# Buttons.net
KiCad netlist of a schematic drawn in EAGLE
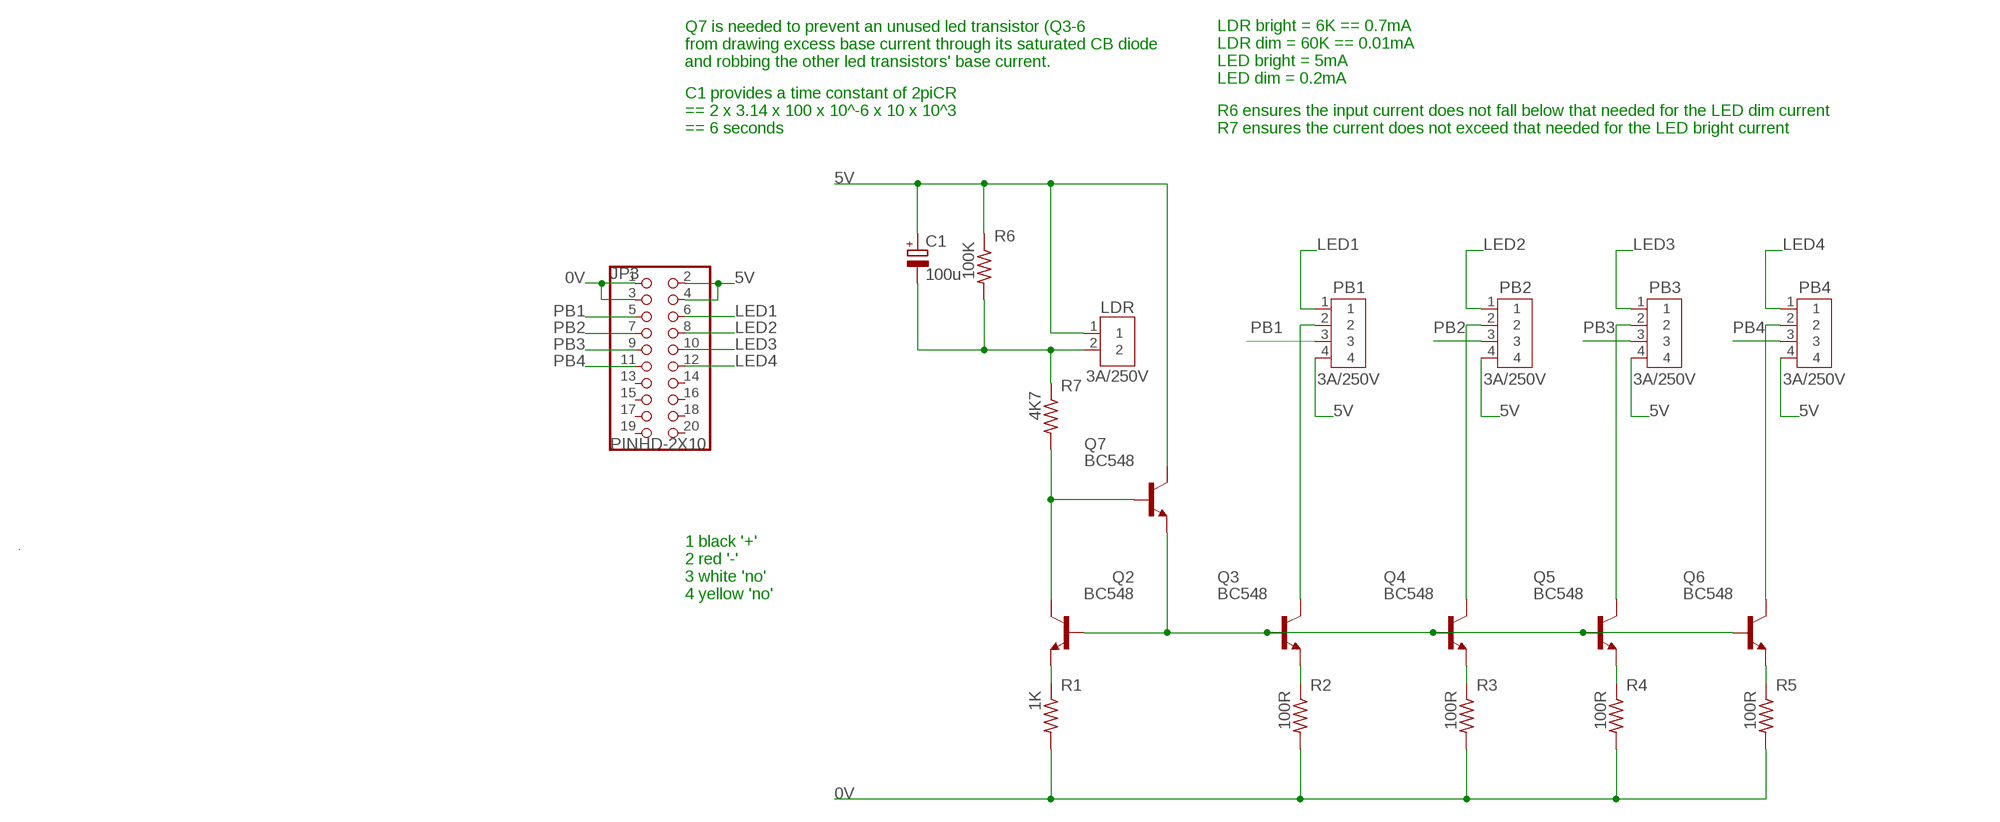
[diagram p0: schematic, sheet 1]

(export (version "E")
  (design (tool "Eeschema 10.0.6"))
  (components
    (comp (ref "C1")
      (value "100u")
      (footprint "eagle-import:E3,5-8")
      (libsource (lib "eagle-import") (part "CPOL-EUE3.5-8"))
    )
    (comp (ref "JP3")
      (value "PINHD-2X10")
      (footprint "eagle-import:2X10")
      (libsource (lib "eagle-import") (part "PINHD-2X10"))
    )
    (comp (ref "LDR")
      (value "3A/250V")
      (footprint "eagle-import:B2B-XH-A")
      (fields (field (name "MANUFACTURER") "JST (XH CONNECTOR)") (field (name "MPN") "B2B-XH-A"))
      (libsource (lib "eagle-import") (part "B2B-XH-A"))
    )
    (comp (ref "PB1")
      (value "3A/250V")
      (footprint "eagle-import:B4B-XH-A")
      (fields (field (name "MANUFACTURER") "JST (XH connector)") (field (name "MPN") "B4B-XH-A"))
      (libsource (lib "eagle-import") (part "B4B-XH-A"))
    )
    (comp (ref "PB2")
      (value "3A/250V")
      (footprint "eagle-import:B4B-XH-A")
      (fields (field (name "MANUFACTURER") "JST (XH connector)") (field (name "MPN") "B4B-XH-A"))
      (libsource (lib "eagle-import") (part "B4B-XH-A"))
    )
    (comp (ref "PB3")
      (value "3A/250V")
      (footprint "eagle-import:B4B-XH-A")
      (fields (field (name "MANUFACTURER") "JST (XH connector)") (field (name "MPN") "B4B-XH-A"))
      (libsource (lib "eagle-import") (part "B4B-XH-A"))
    )
    (comp (ref "PB4")
      (value "3A/250V")
      (footprint "eagle-import:B4B-XH-A")
      (fields (field (name "MANUFACTURER") "JST (XH connector)") (field (name "MPN") "B4B-XH-A"))
      (libsource (lib "eagle-import") (part "B4B-XH-A"))
    )
    (comp (ref "Q2")
      (value "BC548")
      (footprint "eagle-import:TO92-EBC")
      (libsource (lib "eagle-import") (part "BC548"))
    )
    (comp (ref "Q3")
      (value "BC548")
      (footprint "eagle-import:TO92-EBC")
      (libsource (lib "eagle-import") (part "BC548"))
    )
    (comp (ref "Q4")
      (value "BC548")
      (footprint "eagle-import:TO92-EBC")
      (libsource (lib "eagle-import") (part "BC548"))
    )
    (comp (ref "Q5")
      (value "BC548")
      (footprint "eagle-import:TO92-EBC")
      (libsource (lib "eagle-import") (part "BC548"))
    )
    (comp (ref "Q6")
      (value "BC548")
      (footprint "eagle-import:TO92-EBC")
      (libsource (lib "eagle-import") (part "BC548"))
    )
    (comp (ref "Q7")
      (value "BC548")
      (footprint "eagle-import:TO92-EBC")
      (libsource (lib "eagle-import") (part "BC548"))
    )
    (comp (ref "R1")
      (value "1K")
      (footprint "eagle-import:0204_7")
      (libsource (lib "eagle-import") (part "RES_7"))
    )
    (comp (ref "R2")
      (value "100R")
      (footprint "eagle-import:0204_7")
      (libsource (lib "eagle-import") (part "RES_7"))
    )
    (comp (ref "R3")
      (value "100R")
      (footprint "eagle-import:0204_7")
      (libsource (lib "eagle-import") (part "RES_7"))
    )
    (comp (ref "R4")
      (value "100R")
      (footprint "eagle-import:0204_7")
      (libsource (lib "eagle-import") (part "RES_7"))
    )
    (comp (ref "R5")
      (value "100R")
      (footprint "eagle-import:0204_7")
      (libsource (lib "eagle-import") (part "RES_7"))
    )
    (comp (ref "R6")
      (value "100K")
      (footprint "eagle-import:0204_7")
      (libsource (lib "eagle-import") (part "RES_7"))
    )
    (comp (ref "R7")
      (value "4K7")
      (footprint "eagle-import:0204_7")
      (libsource (lib "eagle-import") (part "RES_7"))
    )
  )
  (nets
    (net (code "1") (name "/0V") (class "Default")
      (node (ref "JP3") (pin "1") (pinfunction "1_1") (pintype "passive"))
      (node (ref "JP3") (pin "3") (pinfunction "3_3") (pintype "passive"))
      (node (ref "R1") (pin "2") (pinfunction "2_2") (pintype "passive"))
      (node (ref "R2") (pin "2") (pinfunction "2_2") (pintype "passive"))
      (node (ref "R3") (pin "2") (pinfunction "2_2") (pintype "passive"))
      (node (ref "R4") (pin "2") (pinfunction "2_2") (pintype "passive"))
      (node (ref "R5") (pin "2") (pinfunction "2_2") (pintype "passive"))
    )
    (net (code "2") (name "/5V") (class "Default")
      (node (ref "C1") (pin "+") (pinfunction "+_+") (pintype "passive"))
      (node (ref "JP3") (pin "2") (pinfunction "2_2") (pintype "passive"))
      (node (ref "JP3") (pin "4") (pinfunction "4_4") (pintype "passive"))
      (node (ref "LDR") (pin "1") (pinfunction "1_1") (pintype "bidirectional"))
      (node (ref "PB1") (pin "4") (pinfunction "4_4") (pintype "bidirectional"))
      (node (ref "PB2") (pin "4") (pinfunction "4_4") (pintype "bidirectional"))
      (node (ref "PB3") (pin "4") (pinfunction "4_4") (pintype "bidirectional"))
      (node (ref "PB4") (pin "4") (pinfunction "4_4") (pintype "bidirectional"))
      (node (ref "Q7") (pin "C") (pinfunction "C_C") (pintype "passive"))
      (node (ref "R6") (pin "1") (pinfunction "1_1") (pintype "passive"))
    )
    (net (code "3") (name "/LED1") (class "Default")
      (node (ref "JP3") (pin "6") (pinfunction "6_6") (pintype "passive"))
      (node (ref "PB1") (pin "1") (pinfunction "1_1") (pintype "bidirectional"))
    )
    (net (code "4") (name "/LED2") (class "Default")
      (node (ref "JP3") (pin "8") (pinfunction "8_8") (pintype "passive"))
      (node (ref "PB2") (pin "1") (pinfunction "1_1") (pintype "bidirectional"))
    )
    (net (code "5") (name "/LED3") (class "Default")
      (node (ref "JP3") (pin "10") (pinfunction "10_10") (pintype "passive"))
      (node (ref "PB3") (pin "1") (pinfunction "1_1") (pintype "bidirectional"))
    )
    (net (code "6") (name "/LED4") (class "Default")
      (node (ref "JP3") (pin "12") (pinfunction "12_12") (pintype "passive"))
      (node (ref "PB4") (pin "1") (pinfunction "1_1") (pintype "bidirectional"))
    )
    (net (code "7") (name "/PB1") (class "Default")
      (node (ref "JP3") (pin "5") (pinfunction "5_5") (pintype "passive"))
      (node (ref "PB1") (pin "3") (pinfunction "3_3") (pintype "bidirectional"))
    )
    (net (code "8") (name "/PB2") (class "Default")
      (node (ref "JP3") (pin "7") (pinfunction "7_7") (pintype "passive"))
      (node (ref "PB2") (pin "3") (pinfunction "3_3") (pintype "bidirectional"))
    )
    (net (code "9") (name "/PB3") (class "Default")
      (node (ref "JP3") (pin "9") (pinfunction "9_9") (pintype "passive"))
      (node (ref "PB3") (pin "3") (pinfunction "3_3") (pintype "bidirectional"))
    )
    (net (code "10") (name "/PB4") (class "Default")
      (node (ref "JP3") (pin "11") (pinfunction "11_11") (pintype "passive"))
      (node (ref "PB4") (pin "3") (pinfunction "3_3") (pintype "bidirectional"))
    )
    (net (code "11") (name "Net-(C1-Pad-)") (class "Default")
      (node (ref "C1") (pin "-") (pinfunction "-_-") (pintype "passive"))
      (node (ref "LDR") (pin "2") (pinfunction "2_2") (pintype "bidirectional"))
      (node (ref "R6") (pin "2") (pinfunction "2_2") (pintype "passive"))
      (node (ref "R7") (pin "1") (pinfunction "1_1") (pintype "passive"))
    )
    (net (code "12") (name "Net-(PB1-Pad2)") (class "Default")
      (node (ref "PB1") (pin "2") (pinfunction "2_2") (pintype "bidirectional"))
      (node (ref "Q3") (pin "C") (pinfunction "C_C") (pintype "passive"))
    )
    (net (code "13") (name "Net-(PB2-Pad2)") (class "Default")
      (node (ref "PB2") (pin "2") (pinfunction "2_2") (pintype "bidirectional"))
      (node (ref "Q4") (pin "C") (pinfunction "C_C") (pintype "passive"))
    )
    (net (code "14") (name "Net-(PB3-Pad2)") (class "Default")
      (node (ref "PB3") (pin "2") (pinfunction "2_2") (pintype "bidirectional"))
      (node (ref "Q5") (pin "C") (pinfunction "C_C") (pintype "passive"))
    )
    (net (code "15") (name "Net-(PB4-Pad2)") (class "Default")
      (node (ref "PB4") (pin "2") (pinfunction "2_2") (pintype "bidirectional"))
      (node (ref "Q6") (pin "C") (pinfunction "C_C") (pintype "passive"))
    )
    (net (code "16") (name "Net-(Q2-PadB)") (class "Default")
      (node (ref "Q2") (pin "B") (pinfunction "B_B") (pintype "passive"))
      (node (ref "Q3") (pin "B") (pinfunction "B_B") (pintype "passive"))
      (node (ref "Q4") (pin "B") (pinfunction "B_B") (pintype "passive"))
      (node (ref "Q5") (pin "B") (pinfunction "B_B") (pintype "passive"))
      (node (ref "Q6") (pin "B") (pinfunction "B_B") (pintype "passive"))
      (node (ref "Q7") (pin "E") (pinfunction "E_E") (pintype "passive"))
    )
    (net (code "17") (name "Net-(Q2-PadC)") (class "Default")
      (node (ref "Q2") (pin "C") (pinfunction "C_C") (pintype "passive"))
      (node (ref "Q7") (pin "B") (pinfunction "B_B") (pintype "passive"))
      (node (ref "R7") (pin "2") (pinfunction "2_2") (pintype "passive"))
    )
    (net (code "18") (name "Net-(Q2-PadE)") (class "Default")
      (node (ref "Q2") (pin "E") (pinfunction "E_E") (pintype "passive"))
      (node (ref "R1") (pin "1") (pinfunction "1_1") (pintype "passive"))
    )
    (net (code "19") (name "Net-(Q3-PadE)") (class "Default")
      (node (ref "Q3") (pin "E") (pinfunction "E_E") (pintype "passive"))
      (node (ref "R2") (pin "1") (pinfunction "1_1") (pintype "passive"))
    )
    (net (code "20") (name "Net-(Q4-PadE)") (class "Default")
      (node (ref "Q4") (pin "E") (pinfunction "E_E") (pintype "passive"))
      (node (ref "R3") (pin "1") (pinfunction "1_1") (pintype "passive"))
    )
    (net (code "21") (name "Net-(Q5-PadE)") (class "Default")
      (node (ref "Q5") (pin "E") (pinfunction "E_E") (pintype "passive"))
      (node (ref "R4") (pin "1") (pinfunction "1_1") (pintype "passive"))
    )
    (net (code "22") (name "Net-(Q6-PadE)") (class "Default")
      (node (ref "Q6") (pin "E") (pinfunction "E_E") (pintype "passive"))
      (node (ref "R5") (pin "1") (pinfunction "1_1") (pintype "passive"))
    )
    (net (code "23") (name "unconnected-(JP3-Pad13)") (class "Default")
      (node (ref "JP3") (pin "13") (pinfunction "13_13") (pintype "passive"))
    )
    (net (code "24") (name "unconnected-(JP3-Pad14)") (class "Default")
      (node (ref "JP3") (pin "14") (pinfunction "14_14") (pintype "passive"))
    )
    (net (code "25") (name "unconnected-(JP3-Pad15)") (class "Default")
      (node (ref "JP3") (pin "15") (pinfunction "15_15") (pintype "passive"))
    )
    (net (code "26") (name "unconnected-(JP3-Pad16)") (class "Default")
      (node (ref "JP3") (pin "16") (pinfunction "16_16") (pintype "passive"))
    )
    (net (code "27") (name "unconnected-(JP3-Pad17)") (class "Default")
      (node (ref "JP3") (pin "17") (pinfunction "17_17") (pintype "passive"))
    )
    (net (code "28") (name "unconnected-(JP3-Pad18)") (class "Default")
      (node (ref "JP3") (pin "18") (pinfunction "18_18") (pintype "passive"))
    )
    (net (code "29") (name "unconnected-(JP3-Pad19)") (class "Default")
      (node (ref "JP3") (pin "19") (pinfunction "19_19") (pintype "passive"))
    )
    (net (code "30") (name "unconnected-(JP3-Pad20)") (class "Default")
      (node (ref "JP3") (pin "20") (pinfunction "20_20") (pintype "passive"))
    )
  )
)
